# led_driver_3A.net
KiCad netlist of a schematic drawn in EAGLE
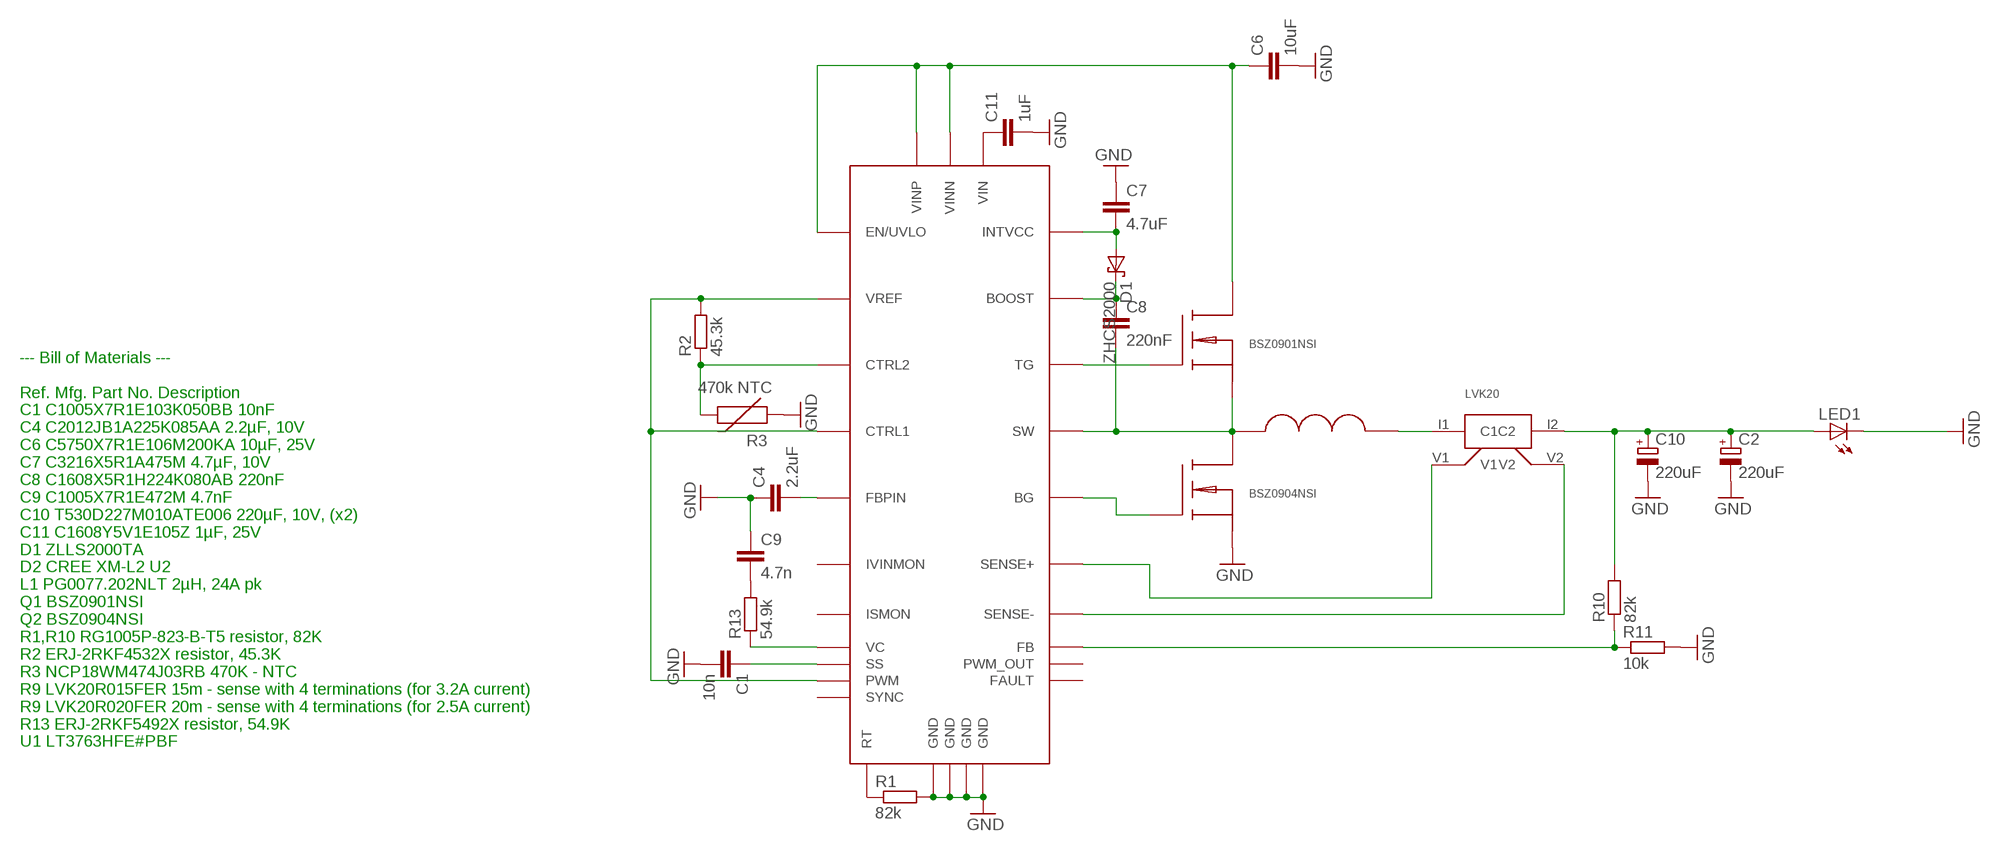
[diagram p0: schematic, sheet 1]

(export (version "E")
  (design (tool "Eeschema 10.0.6"))
  (components
    (comp (ref "C1")
      (value "10n")
      (footprint "eagle-import:C0402")
      (libsource (lib "eagle-import") (part "C-EUC0402"))
    )
    (comp (ref "C2")
      (value "220uF")
      (footprint "eagle-import:SMC_D")
      (libsource (lib "eagle-import") (part "CPOL-EUSMCD"))
    )
    (comp (ref "C4")
      (value "2.2uF")
      (footprint "eagle-import:C0805")
      (libsource (lib "eagle-import") (part "C-EUC0805"))
    )
    (comp (ref "C6")
      (value "10uF")
      (footprint "eagle-import:C2220K")
      (libsource (lib "eagle-import") (part "C-EUC2220K"))
    )
    (comp (ref "C7")
      (value "4.7uF")
      (footprint "eagle-import:C1206")
      (libsource (lib "eagle-import") (part "C-EUC1206"))
    )
    (comp (ref "C8")
      (value "220nF")
      (footprint "eagle-import:C0603")
      (libsource (lib "eagle-import") (part "C-EUC0603"))
    )
    (comp (ref "C9")
      (value "4.7n")
      (footprint "eagle-import:C0402")
      (libsource (lib "eagle-import") (part "C-EUC0402"))
    )
    (comp (ref "C10")
      (value "220uF")
      (footprint "eagle-import:SMC_D")
      (libsource (lib "eagle-import") (part "CPOL-EUSMCD"))
    )
    (comp (ref "C11")
      (value "1uF")
      (footprint "eagle-import:C0603")
      (libsource (lib "eagle-import") (part "C-EUC0603"))
    )
    (comp (ref "D1")
      (value "ZHCS2000")
      (footprint "eagle-import:SOT23-6")
      (libsource (lib "eagle-import") (part "ZHCS2000"))
    )
    (comp (ref "LED1")
      (value "LEDSIDELED")
      (footprint "eagle-import:OSRAM-SIDELED")
      (libsource (lib "eagle-import") (part "LEDSIDELED"))
    )
    (comp (ref "R1")
      (value "82k")
      (footprint "eagle-import:R0402")
      (libsource (lib "eagle-import") (part "R-EU_R0402"))
    )
    (comp (ref "R2")
      (value "45.3k")
      (footprint "eagle-import:R0402")
      (libsource (lib "eagle-import") (part "R-EU_R0402"))
    )
    (comp (ref "R3")
      (value "470k NTC")
      (footprint "eagle-import:0603")
      (libsource (lib "eagle-import") (part "PTC0603"))
    )
    (comp (ref "R10")
      (value "82k")
      (footprint "eagle-import:R0402")
      (libsource (lib "eagle-import") (part "R-EU_R0402"))
    )
    (comp (ref "R11")
      (value "10k")
      (footprint "eagle-import:R0402")
      (libsource (lib "eagle-import") (part "R-EU_R0402"))
    )
    (comp (ref "R13")
      (value "54.9k")
      (footprint "eagle-import:R0402")
      (libsource (lib "eagle-import") (part "R-EU_R0402"))
    )
    (comp (ref "U$1")
      (value "LT3763")
      (footprint "eagle-import:TSSOP-28")
      (libsource (lib "eagle-import") (part "LT3763"))
    )
    (comp (ref "U$2")
      (value "PG0077")
      (footprint "eagle-import:PG0077")
      (libsource (lib "eagle-import") (part "PG0077"))
    )
    (comp (ref "U$3")
      (value "BSZ0901NSI")
      (footprint "eagle-import:BSZ090X")
      (libsource (lib "eagle-import") (part "BSZ090X"))
    )
    (comp (ref "U$4")
      (value "BSZ0904NSI")
      (footprint "eagle-import:BSZ090X")
      (libsource (lib "eagle-import") (part "BSZ090X"))
    )
    (comp (ref "U$5")
      (value "LVK20")
      (footprint "eagle-import:LVK20")
      (libsource (lib "eagle-import") (part "LVK20"))
    )
  )
  (nets
    (net (code "1") (name "GND") (class "Default")
      (node (ref "C1") (pin "2") (pinfunction "2_2") (pintype "passive"))
      (node (ref "C10") (pin "-") (pinfunction "-_-") (pintype "passive"))
      (node (ref "C11") (pin "2") (pinfunction "2_2") (pintype "passive"))
      (node (ref "C2") (pin "-") (pinfunction "-_-") (pintype "passive"))
      (node (ref "C4") (pin "1") (pinfunction "1_1") (pintype "passive"))
      (node (ref "C6") (pin "2") (pinfunction "2_2") (pintype "passive"))
      (node (ref "C7") (pin "1") (pinfunction "1_1") (pintype "passive"))
      (node (ref "C9") (pin "1") (pinfunction "1_1") (pintype "passive"))
      (node (ref "LED1") (pin "C") (pinfunction "C_C") (pintype "passive"))
      (node (ref "R1") (pin "2") (pinfunction "2_2") (pintype "passive"))
      (node (ref "R11") (pin "2") (pinfunction "2_2") (pintype "passive"))
      (node (ref "R3") (pin "1") (pinfunction "1_1") (pintype "bidirectional"))
      (node (ref "U$1") (pin "P$12") (pinfunction "GND_P$12") (pintype "bidirectional"))
      (node (ref "U$1") (pin "P$23") (pinfunction "GND_P$23") (pintype "bidirectional"))
      (node (ref "U$1") (pin "P$28") (pinfunction "GND_P$28") (pintype "bidirectional"))
      (node (ref "U$1") (pin "TH") (pinfunction "GND_TH") (pintype "bidirectional"))
      (node (ref "U$4") (pin "S@1") (pinfunction "S_S@1") (pintype "bidirectional"))
      (node (ref "U$4") (pin "S@2") (pinfunction "S_S@2") (pintype "bidirectional"))
      (node (ref "U$4") (pin "S@3") (pinfunction "S_S@3") (pintype "bidirectional"))
      (node (ref "U$4") (pin "S@4") (pinfunction "S_S@4") (pintype "bidirectional"))
    )
    (net (code "2") (name "Net-(C9-Pad2)") (class "Default")
      (node (ref "C9") (pin "2") (pinfunction "2_2") (pintype "passive"))
      (node (ref "R13") (pin "2") (pinfunction "2_2") (pintype "passive"))
    )
    (net (code "3") (name "Net-(U$1-BG)") (class "Default")
      (node (ref "U$1") (pin "P$1") (pinfunction "BG_P$1") (pintype "bidirectional"))
      (node (ref "U$4") (pin "G") (pinfunction "G_G") (pintype "bidirectional"))
    )
    (net (code "4") (name "Net-(U$1-BOOST)") (class "Default")
      (node (ref "C8") (pin "1") (pinfunction "1_1") (pintype "passive"))
      (node (ref "D1") (pin "1") (pinfunction "K_1") (pintype "passive"))
      (node (ref "D1") (pin "2") (pinfunction "K_2") (pintype "passive"))
      (node (ref "D1") (pin "5") (pinfunction "K_5") (pintype "passive"))
      (node (ref "D1") (pin "6") (pinfunction "K_6") (pintype "passive"))
      (node (ref "U$1") (pin "P$27") (pinfunction "BOOST_P$27") (pintype "bidirectional"))
    )
    (net (code "5") (name "Net-(U$1-CTRL1)") (class "Default")
      (node (ref "R2") (pin "2") (pinfunction "2_2") (pintype "passive"))
      (node (ref "U$1") (pin "P$14") (pinfunction "CTRL1_P$14") (pintype "bidirectional"))
      (node (ref "U$1") (pin "P$22") (pinfunction "PWM_P$22") (pintype "bidirectional"))
      (node (ref "U$1") (pin "P$5") (pinfunction "VREF_P$5") (pintype "bidirectional"))
    )
    (net (code "6") (name "Net-(U$1-CTRL2)") (class "Default")
      (node (ref "R2") (pin "1") (pinfunction "1_1") (pintype "passive"))
      (node (ref "R3") (pin "2") (pinfunction "2_2") (pintype "bidirectional"))
      (node (ref "U$1") (pin "P$13") (pinfunction "CTRL2_P$13") (pintype "bidirectional"))
    )
    (net (code "7") (name "Net-(U$1-EN{slash}UVLO)") (class "Default")
      (node (ref "C6") (pin "1") (pinfunction "1_1") (pintype "passive"))
      (node (ref "U$1") (pin "P$4") (pinfunction "EN/UVLO_P$4") (pintype "bidirectional"))
      (node (ref "U$1") (pin "P$6") (pinfunction "VINN_P$6") (pintype "bidirectional"))
      (node (ref "U$1") (pin "P$7") (pinfunction "VINP_P$7") (pintype "bidirectional"))
      (node (ref "U$3") (pin "D") (pinfunction "D_D") (pintype "bidirectional"))
      (node (ref "U$3") (pin "D@1") (pinfunction "D_D@1") (pintype "bidirectional"))
      (node (ref "U$3") (pin "D@2") (pinfunction "D_D@2") (pintype "bidirectional"))
      (node (ref "U$3") (pin "D@3") (pinfunction "D_D@3") (pintype "bidirectional"))
      (node (ref "U$3") (pin "D@4") (pinfunction "D_D@4") (pintype "bidirectional"))
    )
    (net (code "8") (name "Net-(U$1-FB)") (class "Default")
      (node (ref "R10") (pin "1") (pinfunction "1_1") (pintype "passive"))
      (node (ref "R11") (pin "1") (pinfunction "1_1") (pintype "passive"))
      (node (ref "U$1") (pin "P$11") (pinfunction "FB_P$11") (pintype "bidirectional"))
    )
    (net (code "9") (name "Net-(U$1-FBPIN)") (class "Default")
      (node (ref "C4") (pin "2") (pinfunction "2_2") (pintype "passive"))
      (node (ref "U$1") (pin "P$10") (pinfunction "FBPIN_P$10") (pintype "bidirectional"))
    )
    (net (code "10") (name "Net-(U$1-INTVCC)") (class "Default")
      (node (ref "C7") (pin "2") (pinfunction "2_2") (pintype "passive"))
      (node (ref "D1") (pin "3") (pinfunction "A_3") (pintype "passive"))
      (node (ref "D1") (pin "4") (pinfunction "A_4") (pintype "passive"))
      (node (ref "U$1") (pin "P$2") (pinfunction "INTVCC_P$2") (pintype "bidirectional"))
    )
    (net (code "11") (name "Net-(U$1-RT)") (class "Default")
      (node (ref "R1") (pin "1") (pinfunction "1_1") (pintype "passive"))
      (node (ref "U$1") (pin "P$20") (pinfunction "RT_P$20") (pintype "bidirectional"))
    )
    (net (code "12") (name "Net-(U$1-SENSE+)") (class "Default")
      (node (ref "U$1") (pin "P$17") (pinfunction "SENSE+_P$17") (pintype "bidirectional"))
      (node (ref "U$5") (pin "V1") (pinfunction "V1_V1") (pintype "bidirectional"))
    )
    (net (code "13") (name "Net-(U$1-SENSE-)") (class "Default")
      (node (ref "U$1") (pin "P$16") (pinfunction "SENSE-_P$16") (pintype "bidirectional"))
      (node (ref "U$5") (pin "V2") (pinfunction "V2_V2") (pintype "bidirectional"))
    )
    (net (code "14") (name "Net-(U$1-SS)") (class "Default")
      (node (ref "C1") (pin "1") (pinfunction "1_1") (pintype "passive"))
      (node (ref "U$1") (pin "P$15") (pinfunction "SS_P$15") (pintype "bidirectional"))
    )
    (net (code "15") (name "Net-(U$1-SW)") (class "Default")
      (node (ref "C8") (pin "2") (pinfunction "2_2") (pintype "passive"))
      (node (ref "U$1") (pin "P$26") (pinfunction "SW_P$26") (pintype "bidirectional"))
      (node (ref "U$2") (pin "P$1") (pinfunction "P$1_P$1") (pintype "bidirectional"))
      (node (ref "U$3") (pin "S@1") (pinfunction "S_S@1") (pintype "bidirectional"))
      (node (ref "U$3") (pin "S@2") (pinfunction "S_S@2") (pintype "bidirectional"))
      (node (ref "U$3") (pin "S@3") (pinfunction "S_S@3") (pintype "bidirectional"))
      (node (ref "U$3") (pin "S@4") (pinfunction "S_S@4") (pintype "bidirectional"))
      (node (ref "U$4") (pin "D") (pinfunction "D_D") (pintype "bidirectional"))
      (node (ref "U$4") (pin "D@1") (pinfunction "D_D@1") (pintype "bidirectional"))
      (node (ref "U$4") (pin "D@2") (pinfunction "D_D@2") (pintype "bidirectional"))
      (node (ref "U$4") (pin "D@3") (pinfunction "D_D@3") (pintype "bidirectional"))
      (node (ref "U$4") (pin "D@4") (pinfunction "D_D@4") (pintype "bidirectional"))
    )
    (net (code "16") (name "Net-(U$1-TG)") (class "Default")
      (node (ref "U$1") (pin "P$25") (pinfunction "TG_P$25") (pintype "bidirectional"))
      (node (ref "U$3") (pin "G") (pinfunction "G_G") (pintype "bidirectional"))
    )
    (net (code "17") (name "Net-(U$1-VC)") (class "Default")
      (node (ref "R13") (pin "1") (pinfunction "1_1") (pintype "passive"))
      (node (ref "U$1") (pin "P$18") (pinfunction "VC_P$18") (pintype "bidirectional"))
    )
    (net (code "18") (name "Net-(U$1-VIN)") (class "Default")
      (node (ref "C11") (pin "1") (pinfunction "1_1") (pintype "passive"))
      (node (ref "U$1") (pin "P$3") (pinfunction "VIN_P$3") (pintype "bidirectional"))
    )
    (net (code "19") (name "Net-(U$5-C1)") (class "Default")
      (node (ref "U$2") (pin "P$2") (pinfunction "P$2_P$2") (pintype "bidirectional"))
      (node (ref "U$5") (pin "I1") (pinfunction "C1_I1") (pintype "bidirectional"))
    )
    (net (code "20") (name "Net-(U$5-C2)") (class "Default")
      (node (ref "C10") (pin "+") (pinfunction "+_+") (pintype "passive"))
      (node (ref "C2") (pin "+") (pinfunction "+_+") (pintype "passive"))
      (node (ref "LED1") (pin "A") (pinfunction "A_A") (pintype "passive"))
      (node (ref "R10") (pin "2") (pinfunction "2_2") (pintype "passive"))
      (node (ref "U$5") (pin "I2") (pinfunction "C2_I2") (pintype "bidirectional"))
    )
    (net (code "21") (name "unconnected-(U$1-FAULT-PadP$9)") (class "Default")
      (node (ref "U$1") (pin "P$9") (pinfunction "FAULT_P$9") (pintype "bidirectional"))
    )
    (net (code "22") (name "unconnected-(U$1-ISMON-PadP$19)") (class "Default")
      (node (ref "U$1") (pin "P$19") (pinfunction "ISMON_P$19") (pintype "bidirectional"))
    )
    (net (code "23") (name "unconnected-(U$1-IVINMON-PadP$8)") (class "Default")
      (node (ref "U$1") (pin "P$8") (pinfunction "IVINMON_P$8") (pintype "bidirectional"))
    )
    (net (code "24") (name "unconnected-(U$1-PWM_OUT-PadP$24)") (class "Default")
      (node (ref "U$1") (pin "P$24") (pinfunction "PWM_OUT_P$24") (pintype "bidirectional"))
    )
    (net (code "25") (name "unconnected-(U$1-SYNC-PadP$21)") (class "Default")
      (node (ref "U$1") (pin "P$21") (pinfunction "SYNC_P$21") (pintype "bidirectional"))
    )
  )
)
